# BadgeLedMatrix.net
KiCad netlist of a schematic drawn in EAGLE
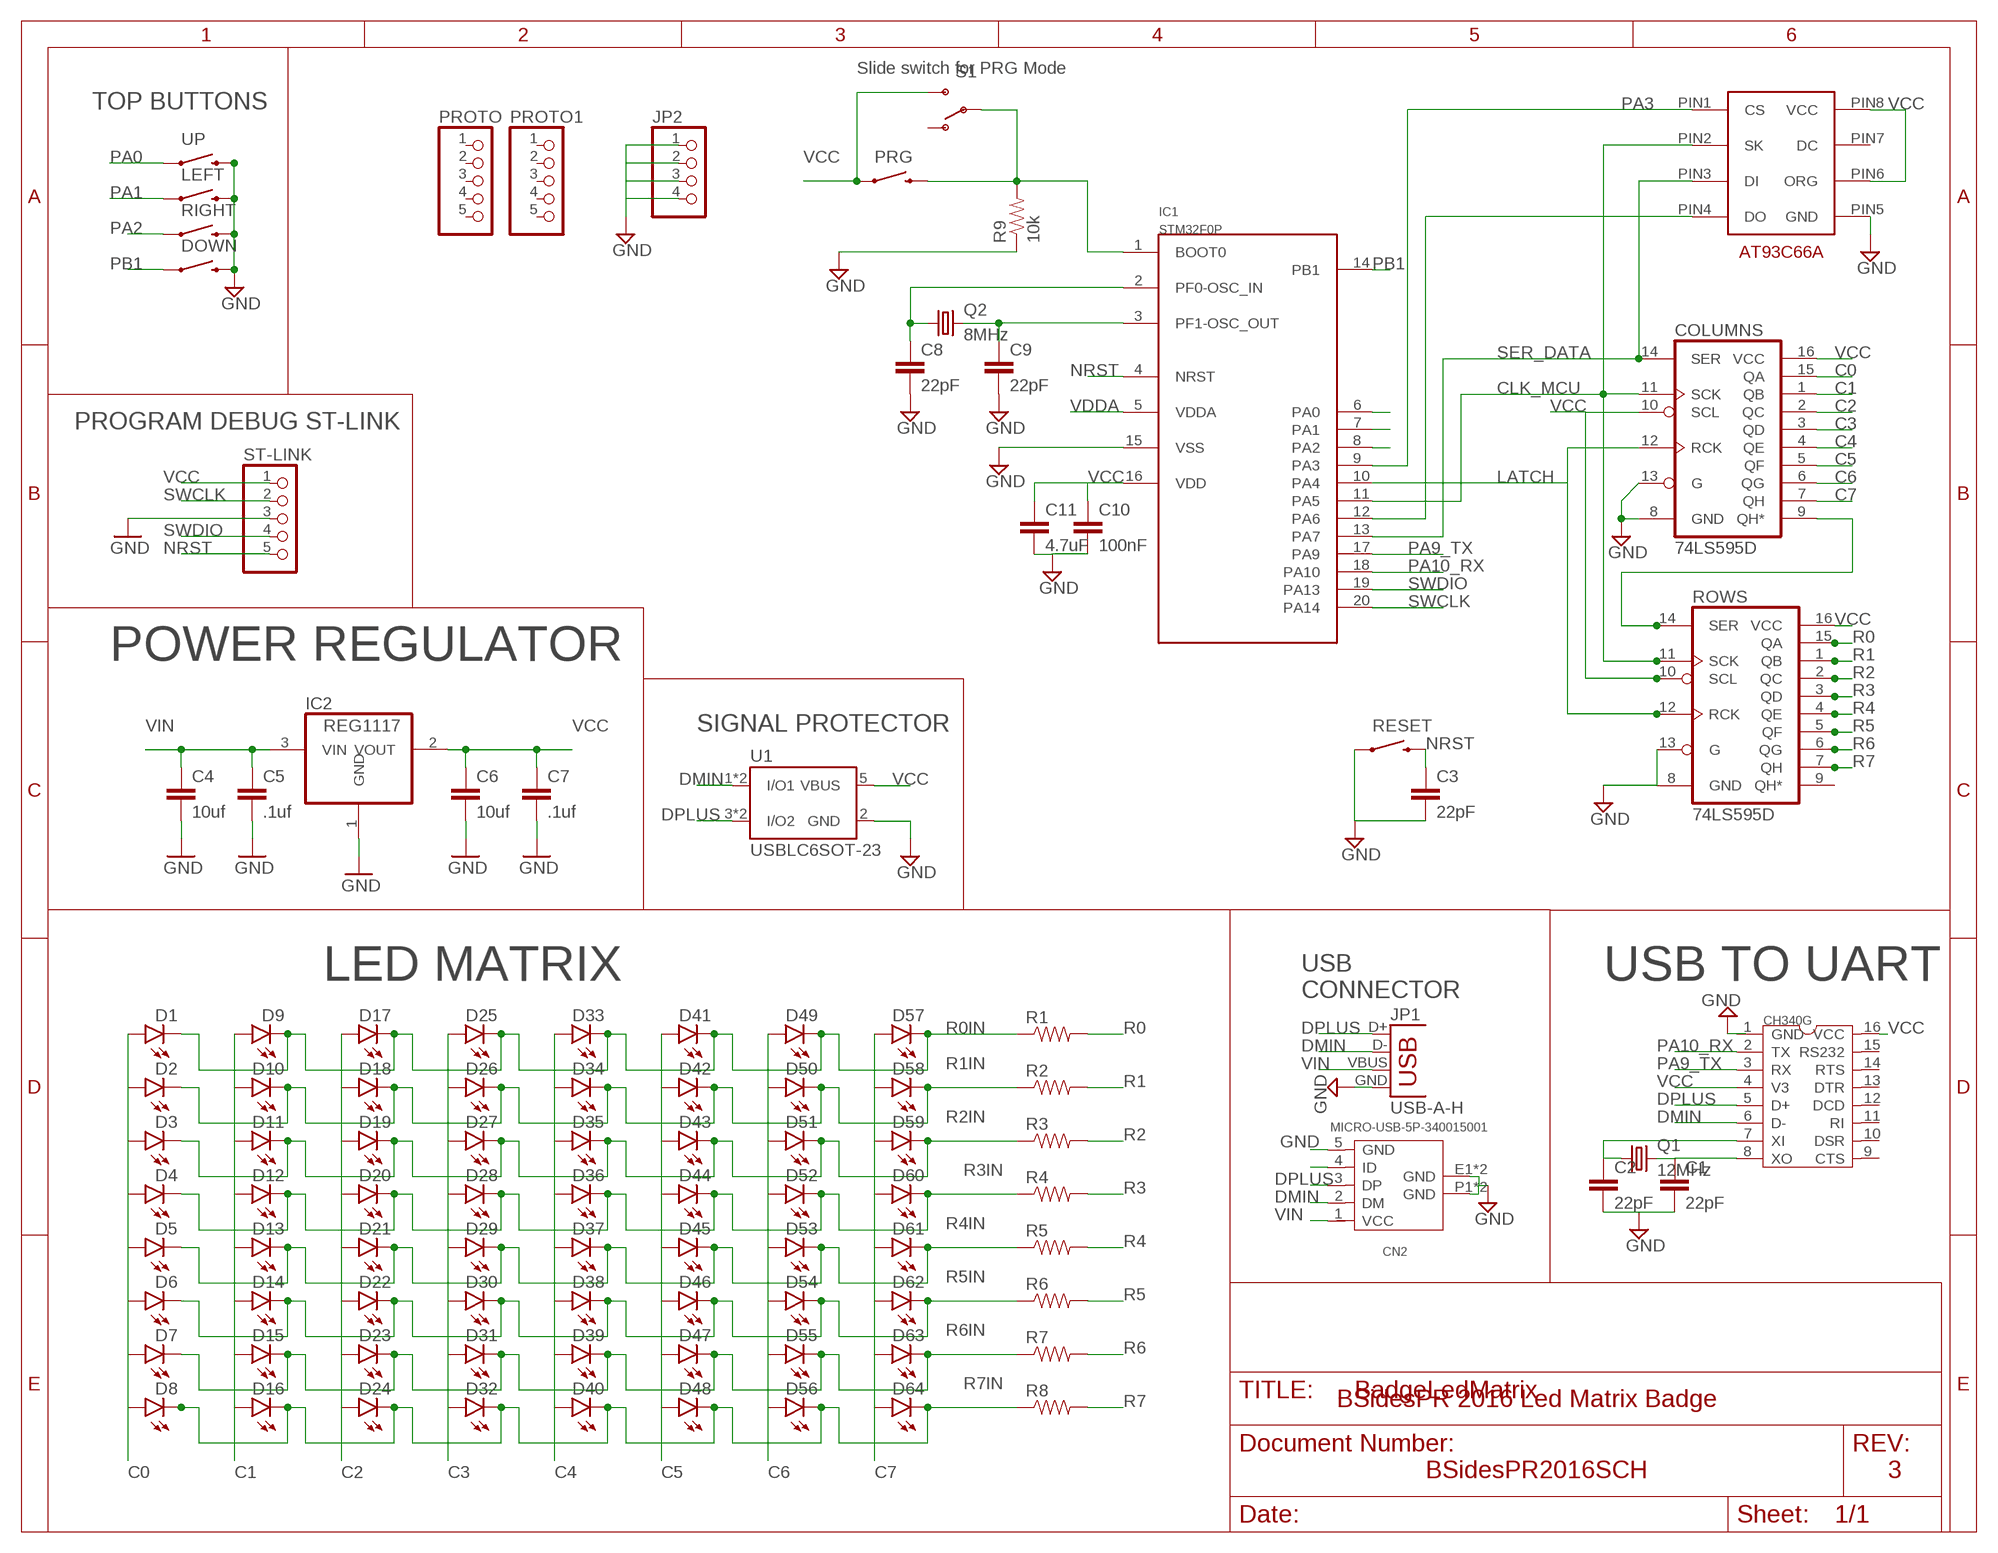
[diagram p0: schematic, sheet 1]

(export (version "E")
  (design (tool "Eeschema 10.0.6"))
  (components
    (comp (ref "C1")
      (value "22pF")
      (footprint "eagle-import:0603-CAP")
      (libsource (lib "eagle-import") (part "CAP0603-CAP"))
    )
    (comp (ref "C2")
      (value "22pF")
      (footprint "eagle-import:0603-CAP")
      (libsource (lib "eagle-import") (part "CAP0603-CAP"))
    )
    (comp (ref "C3")
      (value "22pF")
      (footprint "eagle-import:0603-CAP")
      (libsource (lib "eagle-import") (part "CAP0603-CAP"))
    )
    (comp (ref "C4")
      (value "10uf")
      (footprint "eagle-import:0805")
      (libsource (lib "eagle-import") (part "22UF-6.3V-20%(0805)"))
    )
    (comp (ref "C5")
      (value ".1uf")
      (footprint "eagle-import:0603-CAP")
      (libsource (lib "eagle-import") (part "SparkFun-Passives_CAP0603-CAP"))
    )
    (comp (ref "C6")
      (value "10uf")
      (footprint "eagle-import:0805")
      (libsource (lib "eagle-import") (part "22UF-6.3V-20%(0805)"))
    )
    (comp (ref "C7")
      (value ".1uf")
      (footprint "eagle-import:0603-CAP")
      (libsource (lib "eagle-import") (part "SparkFun-Passives_CAP0603-CAP"))
    )
    (comp (ref "C8")
      (value "22pF")
      (footprint "eagle-import:0603-CAP")
      (libsource (lib "eagle-import") (part "CAP0603-CAP"))
    )
    (comp (ref "C9")
      (value "22pF")
      (footprint "eagle-import:0603-CAP")
      (libsource (lib "eagle-import") (part "CAP0603-CAP"))
    )
    (comp (ref "C10")
      (value "100nF")
      (footprint "eagle-import:0603-CAP")
      (libsource (lib "eagle-import") (part "CAP0603-CAP"))
    )
    (comp (ref "C11")
      (value "4.7uF")
      (footprint "eagle-import:0603-CAP")
      (libsource (lib "eagle-import") (part "CAP0603-CAP"))
    )
    (comp (ref "CH340G")
      (value "CH340GCH340G")
      (footprint "eagle-import:SOP-16")
      (libsource (lib "eagle-import") (part "CH340GCH340G"))
    )
    (comp (ref "CN2")
      (value "MICRO-USB-5P-340015001")
      (footprint "eagle-import:B-SMD-5P")
      (libsource (lib "eagle-import") (part "MICRO-USB-5P-340015001"))
    )
    (comp (ref "COLUMNS")
      (value "74LS595D")
      (footprint "eagle-import:SO16")
      (libsource (lib "eagle-import") (part "74595DLS"))
    )
    (comp (ref "D1")
      (value "LED0603")
      (footprint "eagle-import:LED-0603")
      (libsource (lib "eagle-import") (part "LED0603"))
    )
    (comp (ref "D2")
      (value "LED0603")
      (footprint "eagle-import:LED-0603")
      (libsource (lib "eagle-import") (part "LED0603"))
    )
    (comp (ref "D3")
      (value "LED0603")
      (footprint "eagle-import:LED-0603")
      (libsource (lib "eagle-import") (part "LED0603"))
    )
    (comp (ref "D4")
      (value "LED0603")
      (footprint "eagle-import:LED-0603")
      (libsource (lib "eagle-import") (part "LED0603"))
    )
    (comp (ref "D5")
      (value "LED0603")
      (footprint "eagle-import:LED-0603")
      (libsource (lib "eagle-import") (part "LED0603"))
    )
    (comp (ref "D6")
      (value "LED0603")
      (footprint "eagle-import:LED-0603")
      (libsource (lib "eagle-import") (part "LED0603"))
    )
    (comp (ref "D7")
      (value "LED0603")
      (footprint "eagle-import:LED-0603")
      (libsource (lib "eagle-import") (part "LED0603"))
    )
    (comp (ref "D8")
      (value "LED0603")
      (footprint "eagle-import:LED-0603")
      (libsource (lib "eagle-import") (part "LED0603"))
    )
    (comp (ref "D9")
      (value "LED0603")
      (footprint "eagle-import:LED-0603")
      (libsource (lib "eagle-import") (part "LED0603"))
    )
    (comp (ref "D10")
      (value "LED0603")
      (footprint "eagle-import:LED-0603")
      (libsource (lib "eagle-import") (part "LED0603"))
    )
    (comp (ref "D11")
      (value "LED0603")
      (footprint "eagle-import:LED-0603")
      (libsource (lib "eagle-import") (part "LED0603"))
    )
    (comp (ref "D12")
      (value "LED0603")
      (footprint "eagle-import:LED-0603")
      (libsource (lib "eagle-import") (part "LED0603"))
    )
    (comp (ref "D13")
      (value "LED0603")
      (footprint "eagle-import:LED-0603")
      (libsource (lib "eagle-import") (part "LED0603"))
    )
    (comp (ref "D14")
      (value "LED0603")
      (footprint "eagle-import:LED-0603")
      (libsource (lib "eagle-import") (part "LED0603"))
    )
    (comp (ref "D15")
      (value "LED0603")
      (footprint "eagle-import:LED-0603")
      (libsource (lib "eagle-import") (part "LED0603"))
    )
    (comp (ref "D16")
      (value "LED0603")
      (footprint "eagle-import:LED-0603")
      (libsource (lib "eagle-import") (part "LED0603"))
    )
    (comp (ref "D17")
      (value "LED0603")
      (footprint "eagle-import:LED-0603")
      (libsource (lib "eagle-import") (part "LED0603"))
    )
    (comp (ref "D18")
      (value "LED0603")
      (footprint "eagle-import:LED-0603")
      (libsource (lib "eagle-import") (part "LED0603"))
    )
    (comp (ref "D19")
      (value "LED0603")
      (footprint "eagle-import:LED-0603")
      (libsource (lib "eagle-import") (part "LED0603"))
    )
    (comp (ref "D20")
      (value "LED0603")
      (footprint "eagle-import:LED-0603")
      (libsource (lib "eagle-import") (part "LED0603"))
    )
    (comp (ref "D21")
      (value "LED0603")
      (footprint "eagle-import:LED-0603")
      (libsource (lib "eagle-import") (part "LED0603"))
    )
    (comp (ref "D22")
      (value "LED0603")
      (footprint "eagle-import:LED-0603")
      (libsource (lib "eagle-import") (part "LED0603"))
    )
    (comp (ref "D23")
      (value "LED0603")
      (footprint "eagle-import:LED-0603")
      (libsource (lib "eagle-import") (part "LED0603"))
    )
    (comp (ref "D24")
      (value "LED0603")
      (footprint "eagle-import:LED-0603")
      (libsource (lib "eagle-import") (part "LED0603"))
    )
    (comp (ref "D25")
      (value "LED0603")
      (footprint "eagle-import:LED-0603")
      (libsource (lib "eagle-import") (part "LED0603"))
    )
    (comp (ref "D26")
      (value "LED0603")
      (footprint "eagle-import:LED-0603")
      (libsource (lib "eagle-import") (part "LED0603"))
    )
    (comp (ref "D27")
      (value "LED0603")
      (footprint "eagle-import:LED-0603")
      (libsource (lib "eagle-import") (part "LED0603"))
    )
    (comp (ref "D28")
      (value "LED0603")
      (footprint "eagle-import:LED-0603")
      (libsource (lib "eagle-import") (part "LED0603"))
    )
    (comp (ref "D29")
      (value "LED0603")
      (footprint "eagle-import:LED-0603")
      (libsource (lib "eagle-import") (part "LED0603"))
    )
    (comp (ref "D30")
      (value "LED0603")
      (footprint "eagle-import:LED-0603")
      (libsource (lib "eagle-import") (part "LED0603"))
    )
    (comp (ref "D31")
      (value "LED0603")
      (footprint "eagle-import:LED-0603")
      (libsource (lib "eagle-import") (part "LED0603"))
    )
    (comp (ref "D32")
      (value "LED0603")
      (footprint "eagle-import:LED-0603")
      (libsource (lib "eagle-import") (part "LED0603"))
    )
    (comp (ref "D33")
      (value "LED0603")
      (footprint "eagle-import:LED-0603")
      (libsource (lib "eagle-import") (part "LED0603"))
    )
    (comp (ref "D34")
      (value "LED0603")
      (footprint "eagle-import:LED-0603")
      (libsource (lib "eagle-import") (part "LED0603"))
    )
    (comp (ref "D35")
      (value "LED0603")
      (footprint "eagle-import:LED-0603")
      (libsource (lib "eagle-import") (part "LED0603"))
    )
    (comp (ref "D36")
      (value "LED0603")
      (footprint "eagle-import:LED-0603")
      (libsource (lib "eagle-import") (part "LED0603"))
    )
    (comp (ref "D37")
      (value "LED0603")
      (footprint "eagle-import:LED-0603")
      (libsource (lib "eagle-import") (part "LED0603"))
    )
    (comp (ref "D38")
      (value "LED0603")
      (footprint "eagle-import:LED-0603")
      (libsource (lib "eagle-import") (part "LED0603"))
    )
    (comp (ref "D39")
      (value "LED0603")
      (footprint "eagle-import:LED-0603")
      (libsource (lib "eagle-import") (part "LED0603"))
    )
    (comp (ref "D40")
      (value "LED0603")
      (footprint "eagle-import:LED-0603")
      (libsource (lib "eagle-import") (part "LED0603"))
    )
    (comp (ref "D41")
      (value "LED0603")
      (footprint "eagle-import:LED-0603")
      (libsource (lib "eagle-import") (part "LED0603"))
    )
    (comp (ref "D42")
      (value "LED0603")
      (footprint "eagle-import:LED-0603")
      (libsource (lib "eagle-import") (part "LED0603"))
    )
    (comp (ref "D43")
      (value "LED0603")
      (footprint "eagle-import:LED-0603")
      (libsource (lib "eagle-import") (part "LED0603"))
    )
    (comp (ref "D44")
      (value "LED0603")
      (footprint "eagle-import:LED-0603")
      (libsource (lib "eagle-import") (part "LED0603"))
    )
    (comp (ref "D45")
      (value "LED0603")
      (footprint "eagle-import:LED-0603")
      (libsource (lib "eagle-import") (part "LED0603"))
    )
    (comp (ref "D46")
      (value "LED0603")
      (footprint "eagle-import:LED-0603")
      (libsource (lib "eagle-import") (part "LED0603"))
    )
    (comp (ref "D47")
      (value "LED0603")
      (footprint "eagle-import:LED-0603")
      (libsource (lib "eagle-import") (part "LED0603"))
    )
    (comp (ref "D48")
      (value "LED0603")
      (footprint "eagle-import:LED-0603")
      (libsource (lib "eagle-import") (part "LED0603"))
    )
    (comp (ref "D49")
      (value "LED0603")
      (footprint "eagle-import:LED-0603")
      (libsource (lib "eagle-import") (part "LED0603"))
    )
    (comp (ref "D50")
      (value "LED0603")
      (footprint "eagle-import:LED-0603")
      (libsource (lib "eagle-import") (part "LED0603"))
    )
    (comp (ref "D51")
      (value "LED0603")
      (footprint "eagle-import:LED-0603")
      (libsource (lib "eagle-import") (part "LED0603"))
    )
    (comp (ref "D52")
      (value "LED0603")
      (footprint "eagle-import:LED-0603")
      (libsource (lib "eagle-import") (part "LED0603"))
    )
    (comp (ref "D53")
      (value "LED0603")
      (footprint "eagle-import:LED-0603")
      (libsource (lib "eagle-import") (part "LED0603"))
    )
    (comp (ref "D54")
      (value "LED0603")
      (footprint "eagle-import:LED-0603")
      (libsource (lib "eagle-import") (part "LED0603"))
    )
    (comp (ref "D55")
      (value "LED0603")
      (footprint "eagle-import:LED-0603")
      (libsource (lib "eagle-import") (part "LED0603"))
    )
    (comp (ref "D56")
      (value "LED0603")
      (footprint "eagle-import:LED-0603")
      (libsource (lib "eagle-import") (part "LED0603"))
    )
    (comp (ref "D57")
      (value "LED0603")
      (footprint "eagle-import:LED-0603")
      (libsource (lib "eagle-import") (part "LED0603"))
    )
    (comp (ref "D58")
      (value "LED0603")
      (footprint "eagle-import:LED-0603")
      (libsource (lib "eagle-import") (part "LED0603"))
    )
    (comp (ref "D59")
      (value "LED0603")
      (footprint "eagle-import:LED-0603")
      (libsource (lib "eagle-import") (part "LED0603"))
    )
    (comp (ref "D60")
      (value "LED0603")
      (footprint "eagle-import:LED-0603")
      (libsource (lib "eagle-import") (part "LED0603"))
    )
    (comp (ref "D61")
      (value "LED0603")
      (footprint "eagle-import:LED-0603")
      (libsource (lib "eagle-import") (part "LED0603"))
    )
    (comp (ref "D62")
      (value "LED0603")
      (footprint "eagle-import:LED-0603")
      (libsource (lib "eagle-import") (part "LED0603"))
    )
    (comp (ref "D63")
      (value "LED0603")
      (footprint "eagle-import:LED-0603")
      (libsource (lib "eagle-import") (part "LED0603"))
    )
    (comp (ref "D64")
      (value "LED0603")
      (footprint "eagle-import:LED-0603")
      (libsource (lib "eagle-import") (part "LED0603"))
    )
    (comp (ref "DOWN")
      (value "SWITCH-MOMENTARY-2SMD-REDUNDANT")
      (footprint "eagle-import:TACTILE-SWITCH-SMD")
      (libsource (lib "eagle-import") (part "SWITCH-MOMENTARY-2SMD-REDUNDANT"))
    )
    (comp (ref "IC1")
      (value "STM32F0P")
      (footprint "eagle-import:TSSOP20")
      (libsource (lib "eagle-import") (part "STM32F0P"))
    )
    (comp (ref "IC2")
      (value "REG1117")
      (footprint "eagle-import:SOT223")
      (libsource (lib "eagle-import") (part "REG1117"))
    )
    (comp (ref "JP1")
      (value "USB-A-H")
      (footprint "eagle-import:USB-A-H")
      (libsource (lib "eagle-import") (part "USB-A-H"))
    )
    (comp (ref "JP2")
      (value "PINHD-1X4")
      (footprint "eagle-import:1X04")
      (libsource (lib "eagle-import") (part "PINHD-1X4"))
    )
    (comp (ref "LEFT")
      (value "SWITCH-MOMENTARY-2SMD-REDUNDANT")
      (footprint "eagle-import:TACTILE-SWITCH-SMD")
      (libsource (lib "eagle-import") (part "SWITCH-MOMENTARY-2SMD-REDUNDANT"))
    )
    (comp (ref "PRG")
      (value "SWITCH-MOMENTARY-2SMD-REDUNDANT")
      (footprint "eagle-import:TACTILE-SWITCH-SMD")
      (libsource (lib "eagle-import") (part "SWITCH-MOMENTARY-2SMD-REDUNDANT"))
    )
    (comp (ref "PROTO")
      (value "PINHD-1X5")
      (footprint "eagle-import:1X05")
      (libsource (lib "eagle-import") (part "PINHD-1X5"))
    )
    (comp (ref "PROTO1")
      (value "PINHD-1X5")
      (footprint "eagle-import:1X05")
      (libsource (lib "eagle-import") (part "PINHD-1X5"))
    )
    (comp (ref "Q1")
      (value "12MHz")
      (footprint "eagle-import:HC49U70")
      (libsource (lib "eagle-import") (part "CRYSTALHC49U70"))
    )
    (comp (ref "Q2")
      (value "8MHz")
      (footprint "eagle-import:HC49U70")
      (libsource (lib "eagle-import") (part "CRYSTALHC49U70"))
    )
    (comp (ref "R1")
      (value "RESISTOR0603-RES")
      (footprint "eagle-import:0603-RES")
      (libsource (lib "eagle-import") (part "RESISTOR0603-RES"))
    )
    (comp (ref "R2")
      (value "RESISTOR0603-RES")
      (footprint "eagle-import:0603-RES")
      (libsource (lib "eagle-import") (part "RESISTOR0603-RES"))
    )
    (comp (ref "R3")
      (value "RESISTOR0603-RES")
      (footprint "eagle-import:0603-RES")
      (libsource (lib "eagle-import") (part "RESISTOR0603-RES"))
    )
    (comp (ref "R4")
      (value "RESISTOR0603-RES")
      (footprint "eagle-import:0603-RES")
      (libsource (lib "eagle-import") (part "RESISTOR0603-RES"))
    )
    (comp (ref "R5")
      (value "RESISTOR0603-RES")
      (footprint "eagle-import:0603-RES")
      (libsource (lib "eagle-import") (part "RESISTOR0603-RES"))
    )
    (comp (ref "R6")
      (value "RESISTOR0603-RES")
      (footprint "eagle-import:0603-RES")
      (libsource (lib "eagle-import") (part "RESISTOR0603-RES"))
    )
    (comp (ref "R7")
      (value "RESISTOR0603-RES")
      (footprint "eagle-import:0603-RES")
      (libsource (lib "eagle-import") (part "RESISTOR0603-RES"))
    )
    (comp (ref "R8")
      (value "RESISTOR0603-RES")
      (footprint "eagle-import:0603-RES")
      (libsource (lib "eagle-import") (part "RESISTOR0603-RES"))
    )
    (comp (ref "R9")
      (value "10k")
      (footprint "eagle-import:0603-RES")
      (libsource (lib "eagle-import") (part "RESISTOR0603-RES"))
    )
    (comp (ref "RESET")
      (value "SWITCH-MOMENTARY-2SMD-REDUNDANT")
      (footprint "eagle-import:TACTILE-SWITCH-SMD")
      (libsource (lib "eagle-import") (part "SWITCH-MOMENTARY-2SMD-REDUNDANT"))
    )
    (comp (ref "RIGHT")
      (value "SWITCH-MOMENTARY-2SMD-REDUNDANT")
      (footprint "eagle-import:TACTILE-SWITCH-SMD")
      (libsource (lib "eagle-import") (part "SWITCH-MOMENTARY-2SMD-REDUNDANT"))
    )
    (comp (ref "ROWS")
      (value "74LS595D")
      (footprint "eagle-import:SO16")
      (libsource (lib "eagle-import") (part "74595DLS"))
    )
    (comp (ref "S1")
      (value "SWITCH-SPDT-SMD-A")
      (footprint "eagle-import:SWITCH-SPST-SMD-A")
      (libsource (lib "eagle-import") (part "SWITCH-SPDT-SMD-A"))
    )
    (comp (ref "ST-LINK")
      (value "PINHD-1X5")
      (footprint "eagle-import:1X05")
      (libsource (lib "eagle-import") (part "PINHD-1X5"))
    )
    (comp (ref "U$6")
      (value "AT93C66A")
      (footprint "eagle-import:SOP-8")
      (libsource (lib "eagle-import") (part "AT93C66A"))
    )
    (comp (ref "U1")
      (value "USBLC6SOT-23")
      (footprint "eagle-import:SOT23-6")
      (libsource (lib "eagle-import") (part "USBLC6SOT-23"))
    )
    (comp (ref "UP")
      (value "SWITCH-MOMENTARY-2SMD-REDUNDANT")
      (footprint "eagle-import:TACTILE-SWITCH-SMD")
      (libsource (lib "eagle-import") (part "SWITCH-MOMENTARY-2SMD-REDUNDANT"))
    )
  )
  (nets
    (net (code "1") (name "/C0") (class "Default")
      (node (ref "COLUMNS") (pin "15") (pinfunction "QA_15") (pintype "tri_state"))
      (node (ref "D1") (pin "A") (pinfunction "A_A") (pintype "passive"))
      (node (ref "D2") (pin "A") (pinfunction "A_A") (pintype "passive"))
      (node (ref "D3") (pin "A") (pinfunction "A_A") (pintype "passive"))
      (node (ref "D4") (pin "A") (pinfunction "A_A") (pintype "passive"))
      (node (ref "D5") (pin "A") (pinfunction "A_A") (pintype "passive"))
      (node (ref "D6") (pin "A") (pinfunction "A_A") (pintype "passive"))
      (node (ref "D7") (pin "A") (pinfunction "A_A") (pintype "passive"))
      (node (ref "D8") (pin "A") (pinfunction "A_A") (pintype "passive"))
    )
    (net (code "2") (name "/C1") (class "Default")
      (node (ref "COLUMNS") (pin "1") (pinfunction "QB_1") (pintype "tri_state"))
      (node (ref "D10") (pin "A") (pinfunction "A_A") (pintype "passive"))
      (node (ref "D11") (pin "A") (pinfunction "A_A") (pintype "passive"))
      (node (ref "D12") (pin "A") (pinfunction "A_A") (pintype "passive"))
      (node (ref "D13") (pin "A") (pinfunction "A_A") (pintype "passive"))
      (node (ref "D14") (pin "A") (pinfunction "A_A") (pintype "passive"))
      (node (ref "D15") (pin "A") (pinfunction "A_A") (pintype "passive"))
      (node (ref "D16") (pin "A") (pinfunction "A_A") (pintype "passive"))
      (node (ref "D9") (pin "A") (pinfunction "A_A") (pintype "passive"))
    )
    (net (code "3") (name "/C2") (class "Default")
      (node (ref "COLUMNS") (pin "2") (pinfunction "QC_2") (pintype "tri_state"))
      (node (ref "D17") (pin "A") (pinfunction "A_A") (pintype "passive"))
      (node (ref "D18") (pin "A") (pinfunction "A_A") (pintype "passive"))
      (node (ref "D19") (pin "A") (pinfunction "A_A") (pintype "passive"))
      (node (ref "D20") (pin "A") (pinfunction "A_A") (pintype "passive"))
      (node (ref "D21") (pin "A") (pinfunction "A_A") (pintype "passive"))
      (node (ref "D22") (pin "A") (pinfunction "A_A") (pintype "passive"))
      (node (ref "D23") (pin "A") (pinfunction "A_A") (pintype "passive"))
      (node (ref "D24") (pin "A") (pinfunction "A_A") (pintype "passive"))
    )
    (net (code "4") (name "/C3") (class "Default")
      (node (ref "COLUMNS") (pin "3") (pinfunction "QD_3") (pintype "tri_state"))
      (node (ref "D25") (pin "A") (pinfunction "A_A") (pintype "passive"))
      (node (ref "D26") (pin "A") (pinfunction "A_A") (pintype "passive"))
      (node (ref "D27") (pin "A") (pinfunction "A_A") (pintype "passive"))
      (node (ref "D28") (pin "A") (pinfunction "A_A") (pintype "passive"))
      (node (ref "D29") (pin "A") (pinfunction "A_A") (pintype "passive"))
      (node (ref "D30") (pin "A") (pinfunction "A_A") (pintype "passive"))
      (node (ref "D31") (pin "A") (pinfunction "A_A") (pintype "passive"))
      (node (ref "D32") (pin "A") (pinfunction "A_A") (pintype "passive"))
    )
    (net (code "5") (name "/C4") (class "Default")
      (node (ref "COLUMNS") (pin "4") (pinfunction "QE_4") (pintype "tri_state"))
      (node (ref "D33") (pin "A") (pinfunction "A_A") (pintype "passive"))
      (node (ref "D34") (pin "A") (pinfunction "A_A") (pintype "passive"))
      (node (ref "D35") (pin "A") (pinfunction "A_A") (pintype "passive"))
      (node (ref "D36") (pin "A") (pinfunction "A_A") (pintype "passive"))
      (node (ref "D37") (pin "A") (pinfunction "A_A") (pintype "passive"))
      (node (ref "D38") (pin "A") (pinfunction "A_A") (pintype "passive"))
      (node (ref "D39") (pin "A") (pinfunction "A_A") (pintype "passive"))
      (node (ref "D40") (pin "A") (pinfunction "A_A") (pintype "passive"))
    )
    (net (code "6") (name "/C5") (class "Default")
      (node (ref "COLUMNS") (pin "5") (pinfunction "QF_5") (pintype "tri_state"))
      (node (ref "D41") (pin "A") (pinfunction "A_A") (pintype "passive"))
      (node (ref "D42") (pin "A") (pinfunction "A_A") (pintype "passive"))
      (node (ref "D43") (pin "A") (pinfunction "A_A") (pintype "passive"))
      (node (ref "D44") (pin "A") (pinfunction "A_A") (pintype "passive"))
      (node (ref "D45") (pin "A") (pinfunction "A_A") (pintype "passive"))
      (node (ref "D46") (pin "A") (pinfunction "A_A") (pintype "passive"))
      (node (ref "D47") (pin "A") (pinfunction "A_A") (pintype "passive"))
      (node (ref "D48") (pin "A") (pinfunction "A_A") (pintype "passive"))
    )
    (net (code "7") (name "/C6") (class "Default")
      (node (ref "COLUMNS") (pin "6") (pinfunction "QG_6") (pintype "tri_state"))
      (node (ref "D49") (pin "A") (pinfunction "A_A") (pintype "passive"))
      (node (ref "D50") (pin "A") (pinfunction "A_A") (pintype "passive"))
      (node (ref "D51") (pin "A") (pinfunction "A_A") (pintype "passive"))
      (node (ref "D52") (pin "A") (pinfunction "A_A") (pintype "passive"))
      (node (ref "D53") (pin "A") (pinfunction "A_A") (pintype "passive"))
      (node (ref "D54") (pin "A") (pinfunction "A_A") (pintype "passive"))
      (node (ref "D55") (pin "A") (pinfunction "A_A") (pintype "passive"))
      (node (ref "D56") (pin "A") (pinfunction "A_A") (pintype "passive"))
    )
    (net (code "8") (name "/C7") (class "Default")
      (node (ref "COLUMNS") (pin "7") (pinfunction "QH_7") (pintype "tri_state"))
      (node (ref "D57") (pin "A") (pinfunction "A_A") (pintype "passive"))
      (node (ref "D58") (pin "A") (pinfunction "A_A") (pintype "passive"))
      (node (ref "D59") (pin "A") (pinfunction "A_A") (pintype "passive"))
      (node (ref "D60") (pin "A") (pinfunction "A_A") (pintype "passive"))
      (node (ref "D61") (pin "A") (pinfunction "A_A") (pintype "passive"))
      (node (ref "D62") (pin "A") (pinfunction "A_A") (pintype "passive"))
      (node (ref "D63") (pin "A") (pinfunction "A_A") (pintype "passive"))
      (node (ref "D64") (pin "A") (pinfunction "A_A") (pintype "passive"))
    )
    (net (code "9") (name "/CLK_MCU") (class "Default")
      (node (ref "COLUMNS") (pin "11") (pinfunction "SCK_11") (pintype "input"))
      (node (ref "IC1") (pin "11") (pinfunction "PA5_11") (pintype "bidirectional"))
      (node (ref "ROWS") (pin "11") (pinfunction "SCK_11") (pintype "input"))
      (node (ref "U$6") (pin "PIN2") (pinfunction "SK_PIN2") (pintype "bidirectional"))
    )
    (net (code "10") (name "/DMIN") (class "Default")
      (node (ref "CH340G") (pin "6") (pinfunction "D-_6") (pintype "bidirectional"))
      (node (ref "CN2") (pin "2") (pinfunction "DM_2") (pintype "bidirectional"))
      (node (ref "JP1") (pin "D-") (pinfunction "D-_D-") (pintype "bidirectional"))
      (node (ref "U1") (pin "1") (pinfunction "I/O1_1") (pintype "bidirectional"))
      (node (ref "U1") (pin "4") (pinfunction "I/O1_4") (pintype "bidirectional"))
    )
    (net (code "11") (name "/DPLUS") (class "Default")
      (node (ref "CH340G") (pin "5") (pinfunction "D+_5") (pintype "bidirectional"))
      (node (ref "CN2") (pin "3") (pinfunction "DP_3") (pintype "bidirectional"))
      (node (ref "JP1") (pin "D+") (pinfunction "D+_D+") (pintype "bidirectional"))
      (node (ref "U1") (pin "3") (pinfunction "I/O2_3") (pintype "bidirectional"))
      (node (ref "U1") (pin "6") (pinfunction "I/O2_6") (pintype "bidirectional"))
    )
    (net (code "12") (name "/LATCH") (class "Default")
      (node (ref "COLUMNS") (pin "12") (pinfunction "RCK_12") (pintype "input"))
      (node (ref "IC1") (pin "10") (pinfunction "PA4_10") (pintype "bidirectional"))
      (node (ref "ROWS") (pin "12") (pinfunction "RCK_12") (pintype "input"))
    )
    (net (code "13") (name "/NRST") (class "Default")
      (node (ref "C3") (pin "1") (pinfunction "1_1") (pintype "passive"))
      (node (ref "IC1") (pin "4") (pinfunction "NRST_4") (pintype "bidirectional"))
      (node (ref "RESET") (pin "3") (pinfunction "2_3") (pintype "passive"))
      (node (ref "RESET") (pin "4") (pinfunction "2_4") (pintype "passive"))
      (node (ref "ST-LINK") (pin "5") (pinfunction "5_5") (pintype "passive"))
    )
    (net (code "14") (name "/PA0") (class "Default")
      (node (ref "IC1") (pin "6") (pinfunction "PA0_6") (pintype "bidirectional"))
      (node (ref "UP") (pin "1") (pinfunction "1_1") (pintype "passive"))
      (node (ref "UP") (pin "2") (pinfunction "1_2") (pintype "passive"))
    )
    (net (code "15") (name "/PA1") (class "Default")
      (node (ref "IC1") (pin "7") (pinfunction "PA1_7") (pintype "bidirectional"))
      (node (ref "LEFT") (pin "1") (pinfunction "1_1") (pintype "passive"))
      (node (ref "LEFT") (pin "2") (pinfunction "1_2") (pintype "passive"))
    )
    (net (code "16") (name "/PA2") (class "Default")
      (node (ref "IC1") (pin "8") (pinfunction "PA2_8") (pintype "bidirectional"))
      (node (ref "RIGHT") (pin "1") (pinfunction "1_1") (pintype "passive"))
      (node (ref "RIGHT") (pin "2") (pinfunction "1_2") (pintype "passive"))
    )
    (net (code "17") (name "/PA3") (class "Default")
      (node (ref "IC1") (pin "9") (pinfunction "PA3_9") (pintype "bidirectional"))
      (node (ref "U$6") (pin "PIN1") (pinfunction "CS_PIN1") (pintype "bidirectional"))
    )
    (net (code "18") (name "/PA9_TX") (class "Default")
      (node (ref "CH340G") (pin "3") (pinfunction "RX_3") (pintype "bidirectional"))
      (node (ref "IC1") (pin "17") (pinfunction "PA9_17") (pintype "bidirectional"))
    )
    (net (code "19") (name "/PA10_RX") (class "Default")
      (node (ref "CH340G") (pin "2") (pinfunction "TX_2") (pintype "bidirectional"))
      (node (ref "IC1") (pin "18") (pinfunction "PA10_18") (pintype "bidirectional"))
    )
    (net (code "20") (name "/PB1") (class "Default")
      (node (ref "DOWN") (pin "1") (pinfunction "1_1") (pintype "passive"))
      (node (ref "DOWN") (pin "2") (pinfunction "1_2") (pintype "passive"))
      (node (ref "IC1") (pin "14") (pinfunction "PB1_14") (pintype "bidirectional"))
    )
    (net (code "21") (name "/R0") (class "Default")
      (node (ref "R1") (pin "2") (pinfunction "2_2") (pintype "passive"))
      (node (ref "ROWS") (pin "15") (pinfunction "QA_15") (pintype "tri_state"))
    )
    (net (code "22") (name "/R0IN") (class "Default")
      (node (ref "D1") (pin "C") (pinfunction "C_C") (pintype "passive"))
      (node (ref "D17") (pin "C") (pinfunction "C_C") (pintype "passive"))
      (node (ref "D25") (pin "C") (pinfunction "C_C") (pintype "passive"))
      (node (ref "D33") (pin "C") (pinfunction "C_C") (pintype "passive"))
      (node (ref "D41") (pin "C") (pinfunction "C_C") (pintype "passive"))
      (node (ref "D49") (pin "C") (pinfunction "C_C") (pintype "passive"))
      (node (ref "D57") (pin "C") (pinfunction "C_C") (pintype "passive"))
      (node (ref "D9") (pin "C") (pinfunction "C_C") (pintype "passive"))
      (node (ref "R1") (pin "1") (pinfunction "1_1") (pintype "passive"))
    )
    (net (code "23") (name "/R1") (class "Default")
      (node (ref "R2") (pin "2") (pinfunction "2_2") (pintype "passive"))
      (node (ref "ROWS") (pin "1") (pinfunction "QB_1") (pintype "tri_state"))
    )
    (net (code "24") (name "/R1IN") (class "Default")
      (node (ref "D10") (pin "C") (pinfunction "C_C") (pintype "passive"))
      (node (ref "D18") (pin "C") (pinfunction "C_C") (pintype "passive"))
      (node (ref "D2") (pin "C") (pinfunction "C_C") (pintype "passive"))
      (node (ref "D26") (pin "C") (pinfunction "C_C") (pintype "passive"))
      (node (ref "D34") (pin "C") (pinfunction "C_C") (pintype "passive"))
      (node (ref "D42") (pin "C") (pinfunction "C_C") (pintype "passive"))
      (node (ref "D50") (pin "C") (pinfunction "C_C") (pintype "passive"))
      (node (ref "D58") (pin "C") (pinfunction "C_C") (pintype "passive"))
      (node (ref "R2") (pin "1") (pinfunction "1_1") (pintype "passive"))
    )
    (net (code "25") (name "/R2") (class "Default")
      (node (ref "R3") (pin "2") (pinfunction "2_2") (pintype "passive"))
      (node (ref "ROWS") (pin "2") (pinfunction "QC_2") (pintype "tri_state"))
    )
    (net (code "26") (name "/R2IN") (class "Default")
      (node (ref "D11") (pin "C") (pinfunction "C_C") (pintype "passive"))
      (node (ref "D19") (pin "C") (pinfunction "C_C") (pintype "passive"))
      (node (ref "D27") (pin "C") (pinfunction "C_C") (pintype "passive"))
      (node (ref "D3") (pin "C") (pinfunction "C_C") (pintype "passive"))
      (node (ref "D35") (pin "C") (pinfunction "C_C") (pintype "passive"))
      (node (ref "D43") (pin "C") (pinfunction "C_C") (pintype "passive"))
      (node (ref "D51") (pin "C") (pinfunction "C_C") (pintype "passive"))
      (node (ref "D59") (pin "C") (pinfunction "C_C") (pintype "passive"))
      (node (ref "R3") (pin "1") (pinfunction "1_1") (pintype "passive"))
    )
    (net (code "27") (name "/R3") (class "Default")
      (node (ref "R4") (pin "2") (pinfunction "2_2") (pintype "passive"))
      (node (ref "ROWS") (pin "3") (pinfunction "QD_3") (pintype "tri_state"))
    )
    (net (code "28") (name "/R3IN") (class "Default")
      (node (ref "D12") (pin "C") (pinfunction "C_C") (pintype "passive"))
      (node (ref "D20") (pin "C") (pinfunction "C_C") (pintype "passive"))
      (node (ref "D28") (pin "C") (pinfunction "C_C") (pintype "passive"))
      (node (ref "D36") (pin "C") (pinfunction "C_C") (pintype "passive"))
      (node (ref "D4") (pin "C") (pinfunction "C_C") (pintype "passive"))
      (node (ref "D44") (pin "C") (pinfunction "C_C") (pintype "passive"))
      (node (ref "D52") (pin "C") (pinfunction "C_C") (pintype "passive"))
      (node (ref "D60") (pin "C") (pinfunction "C_C") (pintype "passive"))
      (node (ref "R4") (pin "1") (pinfunction "1_1") (pintype "passive"))
    )
    (net (code "29") (name "/R4") (class "Default")
      (node (ref "R5") (pin "2") (pinfunction "2_2") (pintype "passive"))
      (node (ref "ROWS") (pin "4") (pinfunction "QE_4") (pintype "tri_state"))
    )
    (net (code "30") (name "/R4IN") (class "Default")
      (node (ref "D13") (pin "C") (pinfunction "C_C") (pintype "passive"))
      (node (ref "D21") (pin "C") (pinfunction "C_C") (pintype "passive"))
      (node (ref "D29") (pin "C") (pinfunction "C_C") (pintype "passive"))
      (node (ref "D37") (pin "C") (pinfunction "C_C") (pintype "passive"))
      (node (ref "D45") (pin "C") (pinfunction "C_C") (pintype "passive"))
      (node (ref "D5") (pin "C") (pinfunction "C_C") (pintype "passive"))
      (node (ref "D53") (pin "C") (pinfunction "C_C") (pintype "passive"))
      (node (ref "D61") (pin "C") (pinfunction "C_C") (pintype "passive"))
      (node (ref "R5") (pin "1") (pinfunction "1_1") (pintype "passive"))
    )
    (net (code "31") (name "/R5") (class "Default")
      (node (ref "R6") (pin "2") (pinfunction "2_2") (pintype "passive"))
      (node (ref "ROWS") (pin "5") (pinfunction "QF_5") (pintype "tri_state"))
    )
    (net (code "32") (name "/R5IN") (class "Default")
      (node (ref "D14") (pin "C") (pinfunction "C_C") (pintype "passive"))
      (node (ref "D22") (pin "C") (pinfunction "C_C") (pintype "passive"))
      (node (ref "D30") (pin "C") (pinfunction "C_C") (pintype "passive"))
      (node (ref "D38") (pin "C") (pinfunction "C_C") (pintype "passive"))
      (node (ref "D46") (pin "C") (pinfunction "C_C") (pintype "passive"))
      (node (ref "D54") (pin "C") (pinfunction "C_C") (pintype "passive"))
      (node (ref "D6") (pin "C") (pinfunction "C_C") (pintype "passive"))
      (node (ref "D62") (pin "C") (pinfunction "C_C") (pintype "passive"))
      (node (ref "R6") (pin "1") (pinfunction "1_1") (pintype "passive"))
    )
    (net (code "33") (name "/R6") (class "Default")
      (node (ref "R7") (pin "2") (pinfunction "2_2") (pintype "passive"))
      (node (ref "ROWS") (pin "6") (pinfunction "QG_6") (pintype "tri_state"))
    )
    (net (code "34") (name "/R6IN") (class "Default")
      (node (ref "D15") (pin "C") (pinfunction "C_C") (pintype "passive"))
      (node (ref "D23") (pin "C") (pinfunction "C_C") (pintype "passive"))
      (node (ref "D31") (pin "C") (pinfunction "C_C") (pintype "passive"))
      (node (ref "D39") (pin "C") (pinfunction "C_C") (pintype "passive"))
      (node (ref "D47") (pin "C") (pinfunction "C_C") (pintype "passive"))
      (node (ref "D55") (pin "C") (pinfunction "C_C") (pintype "passive"))
      (node (ref "D63") (pin "C") (pinfunction "C_C") (pintype "passive"))
      (node (ref "D7") (pin "C") (pinfunction "C_C") (pintype "passive"))
      (node (ref "R7") (pin "1") (pinfunction "1_1") (pintype "passive"))
    )
    (net (code "35") (name "/R7") (class "Default")
      (node (ref "R8") (pin "2") (pinfunction "2_2") (pintype "passive"))
      (node (ref "ROWS") (pin "7") (pinfunction "QH_7") (pintype "tri_state"))
    )
    (net (code "36") (name "/R7IN") (class "Default")
      (node (ref "D16") (pin "C") (pinfunction "C_C") (pintype "passive"))
      (node (ref "D24") (pin "C") (pinfunction "C_C") (pintype "passive"))
      (node (ref "D32") (pin "C") (pinfunction "C_C") (pintype "passive"))
      (node (ref "D40") (pin "C") (pinfunction "C_C") (pintype "passive"))
      (node (ref "D48") (pin "C") (pinfunction "C_C") (pintype "passive"))
      (node (ref "D56") (pin "C") (pinfunction "C_C") (pintype "passive"))
      (node (ref "D64") (pin "C") (pinfunction "C_C") (pintype "passive"))
      (node (ref "D8") (pin "C") (pinfunction "C_C") (pintype "passive"))
      (node (ref "R8") (pin "1") (pinfunction "1_1") (pintype "passive"))
    )
    (net (code "37") (name "/RI") (class "Default")
      (node (ref "CH340G") (pin "11") (pinfunction "RI_11") (pintype "power_in"))
    )
    (net (code "38") (name "/SER_DATA") (class "Default")
      (node (ref "COLUMNS") (pin "14") (pinfunction "SER_14") (pintype "input"))
      (node (ref "IC1") (pin "13") (pinfunction "PA7_13") (pintype "bidirectional"))
      (node (ref "U$6") (pin "PIN3") (pinfunction "DI_PIN3") (pintype "bidirectional"))
    )
    (net (code "39") (name "/SWCLK") (class "Default")
      (node (ref "IC1") (pin "20") (pinfunction "PA14_20") (pintype "bidirectional"))
      (node (ref "ST-LINK") (pin "2") (pinfunction "2_2") (pintype "passive"))
    )
    (net (code "40") (name "/SWDIO") (class "Default")
      (node (ref "IC1") (pin "19") (pinfunction "PA13_19") (pintype "bidirectional"))
      (node (ref "ST-LINK") (pin "4") (pinfunction "4_4") (pintype "passive"))
    )
    (net (code "41") (name "/VCC") (class "Default")
      (node (ref "C10") (pin "1") (pinfunction "1_1") (pintype "passive"))
      (node (ref "C11") (pin "1") (pinfunction "1_1") (pintype "passive"))
      (node (ref "C6") (pin "1") (pinfunction "1_1") (pintype "passive"))
      (node (ref "C7") (pin "1") (pinfunction "1_1") (pintype "passive"))
      (node (ref "CH340G") (pin "16") (pinfunction "VCC_16") (pintype "output"))
      (node (ref "CH340G") (pin "4") (pinfunction "V3_4") (pintype "bidirectional"))
      (node (ref "COLUMNS") (pin "10") (pinfunction "SCL_10") (pintype "input"))
      (node (ref "COLUMNS") (pin "16") (pinfunction "VCC_16") (pintype "power_in"))
      (node (ref "IC1") (pin "16") (pinfunction "VDD_16") (pintype "bidirectional"))
      (node (ref "IC2") (pin "2") (pinfunction "VOUT_2") (pintype "output"))
      (node (ref "PRG") (pin "1") (pinfunction "1_1") (pintype "passive"))
      (node (ref "PRG") (pin "2") (pinfunction "1_2") (pintype "passive"))
      (node (ref "ROWS") (pin "10") (pinfunction "SCL_10") (pintype "input"))
      (node (ref "ROWS") (pin "16") (pinfunction "VCC_16") (pintype "power_in"))
      (node (ref "S1") (pin "3") (pinfunction "S_3") (pintype "passive"))
      (node (ref "ST-LINK") (pin "1") (pinfunction "1_1") (pintype "passive"))
      (node (ref "U$6") (pin "PIN6") (pinfunction "ORG_PIN6") (pintype "bidirectional"))
      (node (ref "U$6") (pin "PIN8") (pinfunction "VCC_PIN8") (pintype "bidirectional"))
      (node (ref "U1") (pin "5") (pinfunction "VBUS_5") (pintype "bidirectional"))
    )
    (net (code "42") (name "/VDDA") (class "Default")
      (node (ref "IC1") (pin "5") (pinfunction "VDDA_5") (pintype "bidirectional"))
    )
    (net (code "43") (name "/VIN") (class "Default")
      (node (ref "C4") (pin "1") (pinfunction "1_1") (pintype "passive"))
      (node (ref "C5") (pin "1") (pinfunction "1_1") (pintype "passive"))
      (node (ref "CN2") (pin "1") (pinfunction "VCC_1") (pintype "bidirectional"))
      (node (ref "IC2") (pin "3") (pinfunction "VIN_3") (pintype "input"))
      (node (ref "JP1") (pin "VBUS") (pinfunction "VBUS_VBUS") (pintype "bidirectional"))
    )
    (net (code "44") (name "GND") (class "Default")
      (node (ref "C1") (pin "2") (pinfunction "2_2") (pintype "passive"))
      (node (ref "C10") (pin "2") (pinfunction "2_2") (pintype "passive"))
      (node (ref "C11") (pin "2") (pinfunction "2_2") (pintype "passive"))
      (node (ref "C2") (pin "2") (pinfunction "2_2") (pintype "passive"))
      (node (ref "C3") (pin "2") (pinfunction "2_2") (pintype "passive"))
      (node (ref "C4") (pin "2") (pinfunction "2_2") (pintype "passive"))
      (node (ref "C5") (pin "2") (pinfunction "2_2") (pintype "passive"))
      (node (ref "C6") (pin "2") (pinfunction "2_2") (pintype "passive"))
      (node (ref "C7") (pin "2") (pinfunction "2_2") (pintype "passive"))
      (node (ref "C8") (pin "2") (pinfunction "2_2") (pintype "passive"))
      (node (ref "C9") (pin "2") (pinfunction "2_2") (pintype "passive"))
      (node (ref "CH340G") (pin "1") (pinfunction "GND_1") (pintype "bidirectional"))
      (node (ref "CN2") (pin "5") (pinfunction "GND_5") (pintype "bidirectional"))
      (node (ref "CN2") (pin "E1") (pinfunction "GND_E1") (pintype "bidirectional"))
      (node (ref "CN2") (pin "E2") (pinfunction "GND_E2") (pintype "bidirectional"))
      (node (ref "CN2") (pin "P1") (pinfunction "GND_P1") (pintype "bidirectional"))
      (node (ref "CN2") (pin "P2") (pinfunction "GND_P2") (pintype "bidirectional"))
      (node (ref "COLUMNS") (pin "13") (pinfunction "G_13") (pintype "input"))
      (node (ref "COLUMNS") (pin "8") (pinfunction "GND_8") (pintype "power_in"))
      (node (ref "DOWN") (pin "3") (pinfunction "2_3") (pintype "passive"))
      (node (ref "DOWN") (pin "4") (pinfunction "2_4") (pintype "passive"))
      (node (ref "IC1") (pin "15") (pinfunction "VSS_15") (pintype "bidirectional"))
      (node (ref "IC2") (pin "1") (pinfunction "GND_1") (pintype "power_in"))
      (node (ref "JP1") (pin "GND") (pinfunction "GND_GND") (pintype "bidirectional"))
      (node (ref "JP2") (pin "1") (pinfunction "1_1") (pintype "passive"))
      (node (ref "JP2") (pin "2") (pinfunction "2_2") (pintype "passive"))
      (node (ref "JP2") (pin "3") (pinfunction "3_3") (pintype "passive"))
      (node (ref "JP2") (pin "4") (pinfunction "4_4") (pintype "passive"))
      (node (ref "LEFT") (pin "3") (pinfunction "2_3") (pintype "passive"))
      (node (ref "LEFT") (pin "4") (pinfunction "2_4") (pintype "passive"))
      (node (ref "R9") (pin "1") (pinfunction "1_1") (pintype "passive"))
      (node (ref "RESET") (pin "1") (pinfunction "1_1") (pintype "passive"))
      (node (ref "RESET") (pin "2") (pinfunction "1_2") (pintype "passive"))
      (node (ref "RIGHT") (pin "3") (pinfunction "2_3") (pintype "passive"))
      (node (ref "RIGHT") (pin "4") (pinfunction "2_4") (pintype "passive"))
      (node (ref "ROWS") (pin "13") (pinfunction "G_13") (pintype "input"))
      (node (ref "ROWS") (pin "8") (pinfunction "GND_8") (pintype "power_in"))
      (node (ref "ST-LINK") (pin "3") (pinfunction "3_3") (pintype "passive"))
      (node (ref "U$6") (pin "PIN5") (pinfunction "GND_PIN5") (pintype "bidirectional"))
      (node (ref "U1") (pin "2") (pinfunction "GND_2") (pintype "bidirectional"))
      (node (ref "UP") (pin "3") (pinfunction "2_3") (pintype "passive"))
      (node (ref "UP") (pin "4") (pinfunction "2_4") (pintype "passive"))
    )
    (net (code "45") (name "Net-(CH340G-XI)") (class "Default")
      (node (ref "C2") (pin "1") (pinfunction "1_1") (pintype "passive"))
      (node (ref "CH340G") (pin "7") (pinfunction "XI_7") (pintype "power_in"))
      (node (ref "Q1") (pin "1") (pinfunction "1_1") (pintype "passive"))
    )
    (net (code "46") (name "Net-(CH340G-XO)") (class "Default")
      (node (ref "C1") (pin "1") (pinfunction "1_1") (pintype "passive"))
      (node (ref "CH340G") (pin "8") (pinfunction "XO_8") (pintype "input"))
      (node (ref "Q1") (pin "2") (pinfunction "2_2") (pintype "passive"))
    )
    (net (code "47") (name "Net-(COLUMNS-QH*)") (class "Default")
      (node (ref "COLUMNS") (pin "9") (pinfunction "QH*_9") (pintype "tri_state"))
      (node (ref "ROWS") (pin "14") (pinfunction "SER_14") (pintype "input"))
    )
    (net (code "48") (name "Net-(IC1-BOOT0)") (class "Default")
      (node (ref "IC1") (pin "1") (pinfunction "BOOT0_1") (pintype "bidirectional"))
      (node (ref "PRG") (pin "3") (pinfunction "2_3") (pintype "passive"))
      (node (ref "PRG") (pin "4") (pinfunction "2_4") (pintype "passive"))
      (node (ref "R9") (pin "2") (pinfunction "2_2") (pintype "passive"))
      (node (ref "S1") (pin "2") (pinfunction "P_2") (pintype "passive"))
    )
    (net (code "49") (name "Net-(IC1-PA6)") (class "Default")
      (node (ref "IC1") (pin "12") (pinfunction "PA6_12") (pintype "bidirectional"))
      (node (ref "U$6") (pin "PIN4") (pinfunction "DO_PIN4") (pintype "bidirectional"))
    )
    (net (code "50") (name "Net-(IC1-PF0-OSC_IN)") (class "Default")
      (node (ref "C8") (pin "1") (pinfunction "1_1") (pintype "passive"))
      (node (ref "IC1") (pin "2") (pinfunction "PF0-OSC_IN_2") (pintype "bidirectional"))
      (node (ref "Q2") (pin "1") (pinfunction "1_1") (pintype "passive"))
    )
    (net (code "51") (name "Net-(IC1-PF1-OSC_OUT)") (class "Default")
      (node (ref "C9") (pin "1") (pinfunction "1_1") (pintype "passive"))
      (node (ref "IC1") (pin "3") (pinfunction "PF1-OSC_OUT_3") (pintype "bidirectional"))
      (node (ref "Q2") (pin "2") (pinfunction "2_2") (pintype "passive"))
    )
    (net (code "52") (name "unconnected-(CH340G-CTS-Pad9)") (class "Default")
      (node (ref "CH340G") (pin "9") (pinfunction "CTS_9") (pintype "bidirectional"))
    )
    (net (code "53") (name "unconnected-(CH340G-DCD-Pad12)") (class "Default")
      (node (ref "CH340G") (pin "12") (pinfunction "DCD_12") (pintype "output"))
    )
    (net (code "54") (name "unconnected-(CH340G-DSR-Pad10)") (class "Default")
      (node (ref "CH340G") (pin "10") (pinfunction "DSR_10") (pintype "bidirectional"))
    )
    (net (code "55") (name "unconnected-(CH340G-DTR-Pad13)") (class "Default")
      (node (ref "CH340G") (pin "13") (pinfunction "DTR_13") (pintype "input"))
    )
    (net (code "56") (name "unconnected-(CH340G-RS232-Pad15)") (class "Default")
      (node (ref "CH340G") (pin "15") (pinfunction "RS232_15") (pintype "input"))
    )
    (net (code "57") (name "unconnected-(CH340G-RTS-Pad14)") (class "Default")
      (node (ref "CH340G") (pin "14") (pinfunction "RTS_14") (pintype "input"))
    )
    (net (code "58") (name "unconnected-(CN2-ID-Pad4)") (class "Default")
      (node (ref "CN2") (pin "4") (pinfunction "ID_4") (pintype "bidirectional"))
    )
    (net (code "59") (name "unconnected-(PROTO-Pad1)") (class "Default")
      (node (ref "PROTO") (pin "1") (pinfunction "1_1") (pintype "passive"))
    )
    (net (code "60") (name "unconnected-(PROTO-Pad2)") (class "Default")
      (node (ref "PROTO") (pin "2") (pinfunction "2_2") (pintype "passive"))
    )
    (net (code "61") (name "unconnected-(PROTO-Pad3)") (class "Default")
      (node (ref "PROTO") (pin "3") (pinfunction "3_3") (pintype "passive"))
    )
    (net (code "62") (name "unconnected-(PROTO-Pad4)") (class "Default")
      (node (ref "PROTO") (pin "4") (pinfunction "4_4") (pintype "passive"))
    )
    (net (code "63") (name "unconnected-(PROTO-Pad5)") (class "Default")
      (node (ref "PROTO") (pin "5") (pinfunction "5_5") (pintype "passive"))
    )
    (net (code "64") (name "unconnected-(PROTO1-Pad1)") (class "Default")
      (node (ref "PROTO1") (pin "1") (pinfunction "1_1") (pintype "passive"))
    )
    (net (code "65") (name "unconnected-(PROTO1-Pad2)") (class "Default")
      (node (ref "PROTO1") (pin "2") (pinfunction "2_2") (pintype "passive"))
    )
    (net (code "66") (name "unconnected-(PROTO1-Pad3)") (class "Default")
      (node (ref "PROTO1") (pin "3") (pinfunction "3_3") (pintype "passive"))
    )
    (net (code "67") (name "unconnected-(PROTO1-Pad4)") (class "Default")
      (node (ref "PROTO1") (pin "4") (pinfunction "4_4") (pintype "passive"))
    )
    (net (code "68") (name "unconnected-(PROTO1-Pad5)") (class "Default")
      (node (ref "PROTO1") (pin "5") (pinfunction "5_5") (pintype "passive"))
    )
    (net (code "69") (name "unconnected-(ROWS-QH*-Pad9)") (class "Default")
      (node (ref "ROWS") (pin "9") (pinfunction "QH*_9") (pintype "tri_state"))
    )
    (net (code "70") (name "unconnected-(S1-O-Pad1)") (class "Default")
      (node (ref "S1") (pin "1") (pinfunction "O_1") (pintype "passive"))
    )
    (net (code "71") (name "unconnected-(U$6-DC-PadPIN7)") (class "Default")
      (node (ref "U$6") (pin "PIN7") (pinfunction "DC_PIN7") (pintype "bidirectional"))
    )
  )
)
